# rj45_jumper_box.net
KiCad netlist of a schematic drawn in EAGLE
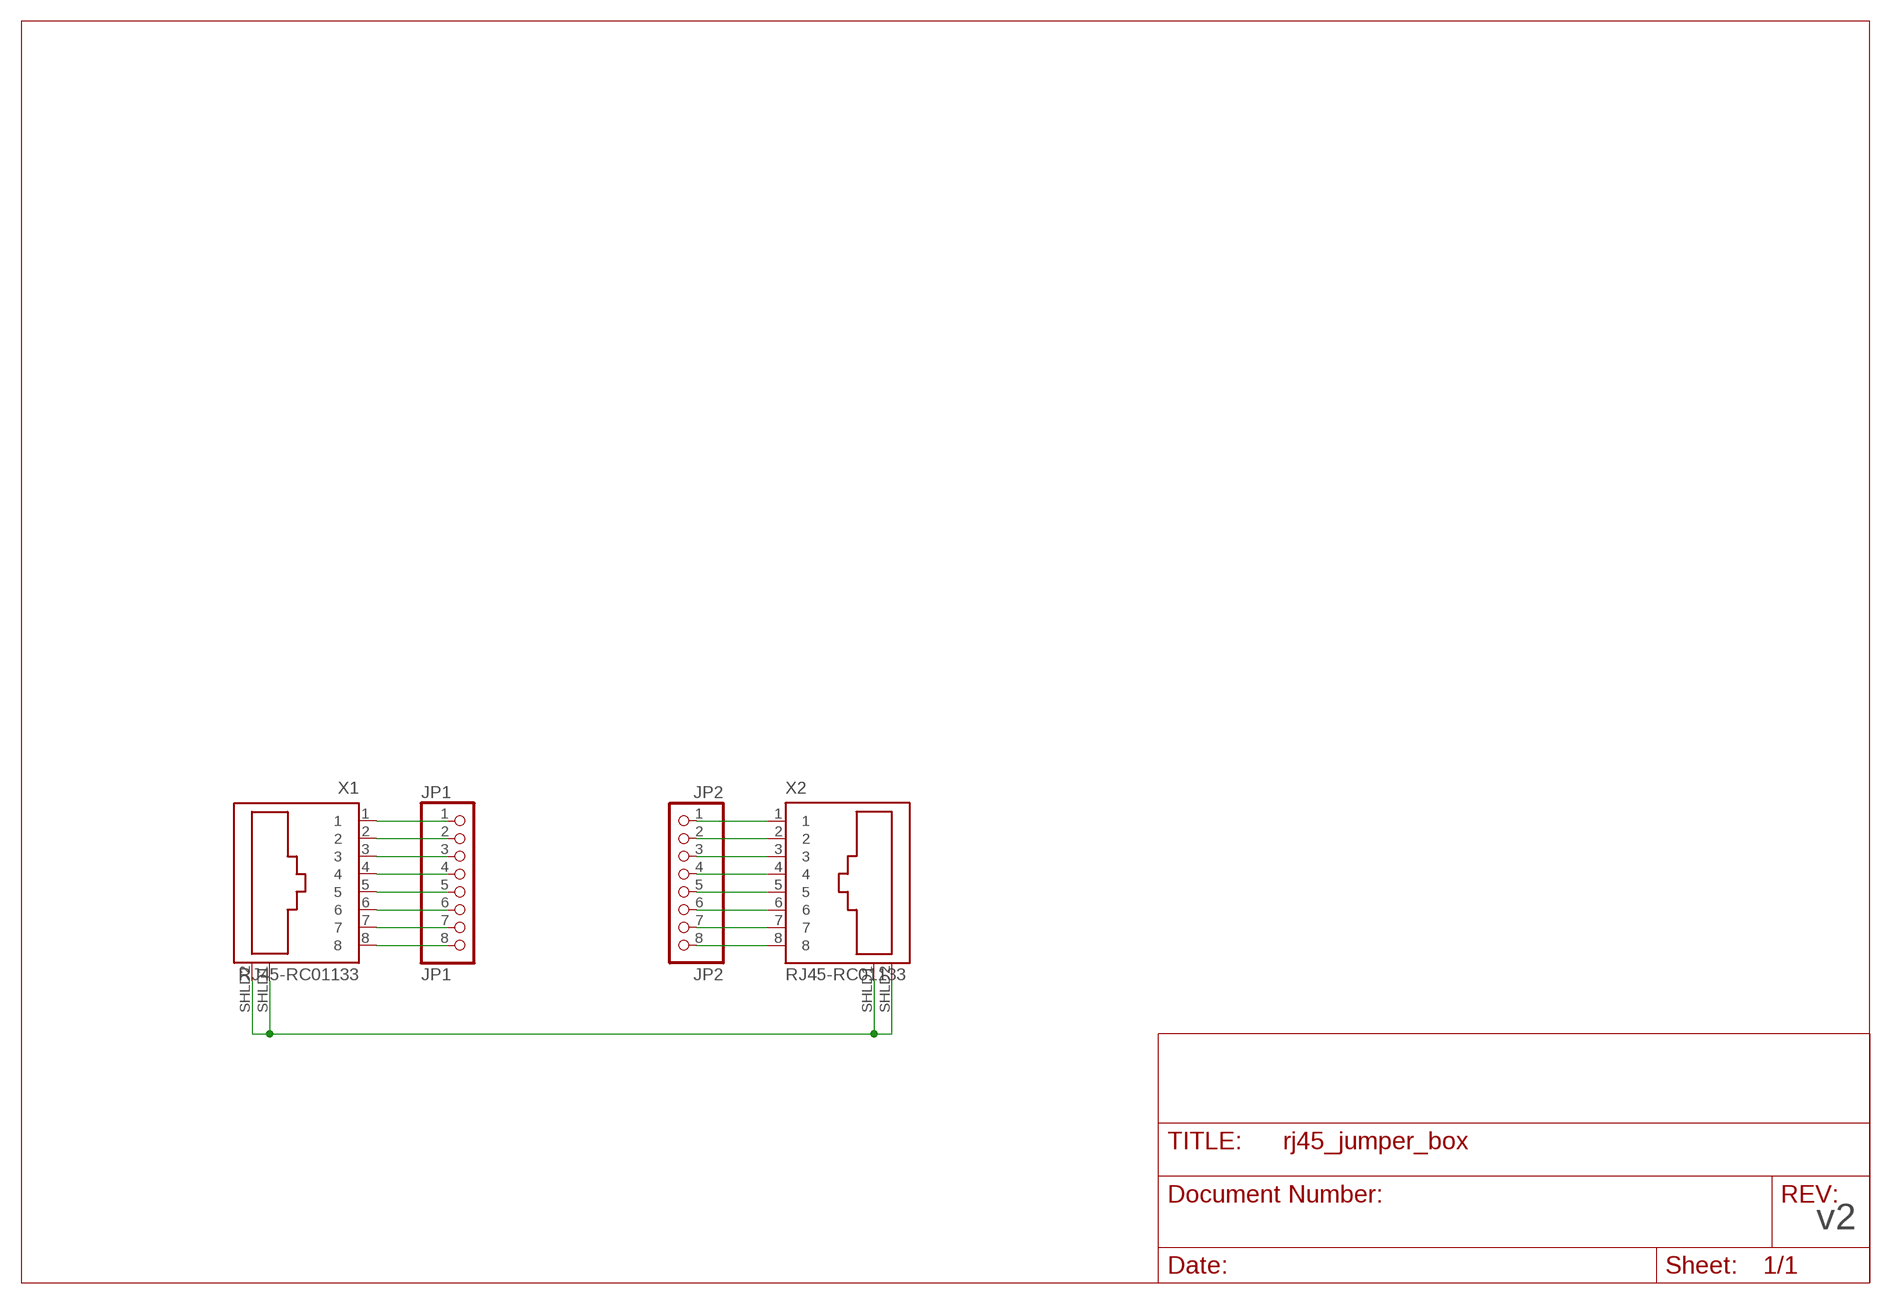
[diagram p0: schematic, sheet 1]

(export (version "E")
  (design (tool "Eeschema 10.0.6"))
  (components
    (comp (ref "JP1")
      (value "JP1")
      (footprint "eagle-import:1X08")
      (libsource (lib "eagle-import") (part "PINHD-1X8"))
    )
    (comp (ref "JP2")
      (value "JP2")
      (footprint "eagle-import:1X08")
      (libsource (lib "eagle-import") (part "PINHD-1X8"))
    )
    (comp (ref "X1")
      (value "RJ45-RC01133")
      (footprint "eagle-import:RC01133")
      (libsource (lib "eagle-import") (part "RJ45-RC01133"))
    )
    (comp (ref "X2")
      (value "RJ45-RC01133")
      (footprint "eagle-import:RC01133")
      (libsource (lib "eagle-import") (part "RJ45-RC01133"))
    )
  )
  (nets
    (net (code "1") (name "Net-(JP1-Pad1)") (class "Default")
      (node (ref "JP1") (pin "1") (pinfunction "1_1") (pintype "passive"))
      (node (ref "X1") (pin "1") (pinfunction "1_1") (pintype "passive"))
    )
    (net (code "2") (name "Net-(JP1-Pad2)") (class "Default")
      (node (ref "JP1") (pin "2") (pinfunction "2_2") (pintype "passive"))
      (node (ref "X1") (pin "2") (pinfunction "2_2") (pintype "passive"))
    )
    (net (code "3") (name "Net-(JP1-Pad3)") (class "Default")
      (node (ref "JP1") (pin "3") (pinfunction "3_3") (pintype "passive"))
      (node (ref "X1") (pin "3") (pinfunction "3_3") (pintype "passive"))
    )
    (net (code "4") (name "Net-(JP1-Pad4)") (class "Default")
      (node (ref "JP1") (pin "4") (pinfunction "4_4") (pintype "passive"))
      (node (ref "X1") (pin "4") (pinfunction "4_4") (pintype "passive"))
    )
    (net (code "5") (name "Net-(JP1-Pad5)") (class "Default")
      (node (ref "JP1") (pin "5") (pinfunction "5_5") (pintype "passive"))
      (node (ref "X1") (pin "5") (pinfunction "5_5") (pintype "passive"))
    )
    (net (code "6") (name "Net-(JP1-Pad6)") (class "Default")
      (node (ref "JP1") (pin "6") (pinfunction "6_6") (pintype "passive"))
      (node (ref "X1") (pin "6") (pinfunction "6_6") (pintype "passive"))
    )
    (net (code "7") (name "Net-(JP1-Pad7)") (class "Default")
      (node (ref "JP1") (pin "7") (pinfunction "7_7") (pintype "passive"))
      (node (ref "X1") (pin "7") (pinfunction "7_7") (pintype "passive"))
    )
    (net (code "8") (name "Net-(JP1-Pad8)") (class "Default")
      (node (ref "JP1") (pin "8") (pinfunction "8_8") (pintype "passive"))
      (node (ref "X1") (pin "8") (pinfunction "8_8") (pintype "passive"))
    )
    (net (code "9") (name "Net-(JP2-Pad1)") (class "Default")
      (node (ref "JP2") (pin "1") (pinfunction "1_1") (pintype "passive"))
      (node (ref "X2") (pin "1") (pinfunction "1_1") (pintype "passive"))
    )
    (net (code "10") (name "Net-(JP2-Pad2)") (class "Default")
      (node (ref "JP2") (pin "2") (pinfunction "2_2") (pintype "passive"))
      (node (ref "X2") (pin "2") (pinfunction "2_2") (pintype "passive"))
    )
    (net (code "11") (name "Net-(JP2-Pad3)") (class "Default")
      (node (ref "JP2") (pin "3") (pinfunction "3_3") (pintype "passive"))
      (node (ref "X2") (pin "3") (pinfunction "3_3") (pintype "passive"))
    )
    (net (code "12") (name "Net-(JP2-Pad4)") (class "Default")
      (node (ref "JP2") (pin "4") (pinfunction "4_4") (pintype "passive"))
      (node (ref "X2") (pin "4") (pinfunction "4_4") (pintype "passive"))
    )
    (net (code "13") (name "Net-(JP2-Pad5)") (class "Default")
      (node (ref "JP2") (pin "5") (pinfunction "5_5") (pintype "passive"))
      (node (ref "X2") (pin "5") (pinfunction "5_5") (pintype "passive"))
    )
    (net (code "14") (name "Net-(JP2-Pad6)") (class "Default")
      (node (ref "JP2") (pin "6") (pinfunction "6_6") (pintype "passive"))
      (node (ref "X2") (pin "6") (pinfunction "6_6") (pintype "passive"))
    )
    (net (code "15") (name "Net-(JP2-Pad7)") (class "Default")
      (node (ref "JP2") (pin "7") (pinfunction "7_7") (pintype "passive"))
      (node (ref "X2") (pin "7") (pinfunction "7_7") (pintype "passive"))
    )
    (net (code "16") (name "Net-(JP2-Pad8)") (class "Default")
      (node (ref "JP2") (pin "8") (pinfunction "8_8") (pintype "passive"))
      (node (ref "X2") (pin "8") (pinfunction "8_8") (pintype "passive"))
    )
    (net (code "17") (name "Net-(X1-S1)") (class "Default")
      (node (ref "X1") (pin "SHLD1") (pinfunction "S1_SHLD1") (pintype "passive"))
      (node (ref "X1") (pin "SHLD2") (pinfunction "S2_SHLD2") (pintype "passive"))
      (node (ref "X2") (pin "SHLD1") (pinfunction "S1_SHLD1") (pintype "passive"))
      (node (ref "X2") (pin "SHLD2") (pinfunction "S2_SHLD2") (pintype "passive"))
    )
  )
)
